# fpga03-serdes-power.net
KiCad netlist of a schematic drawn in Altium Designer
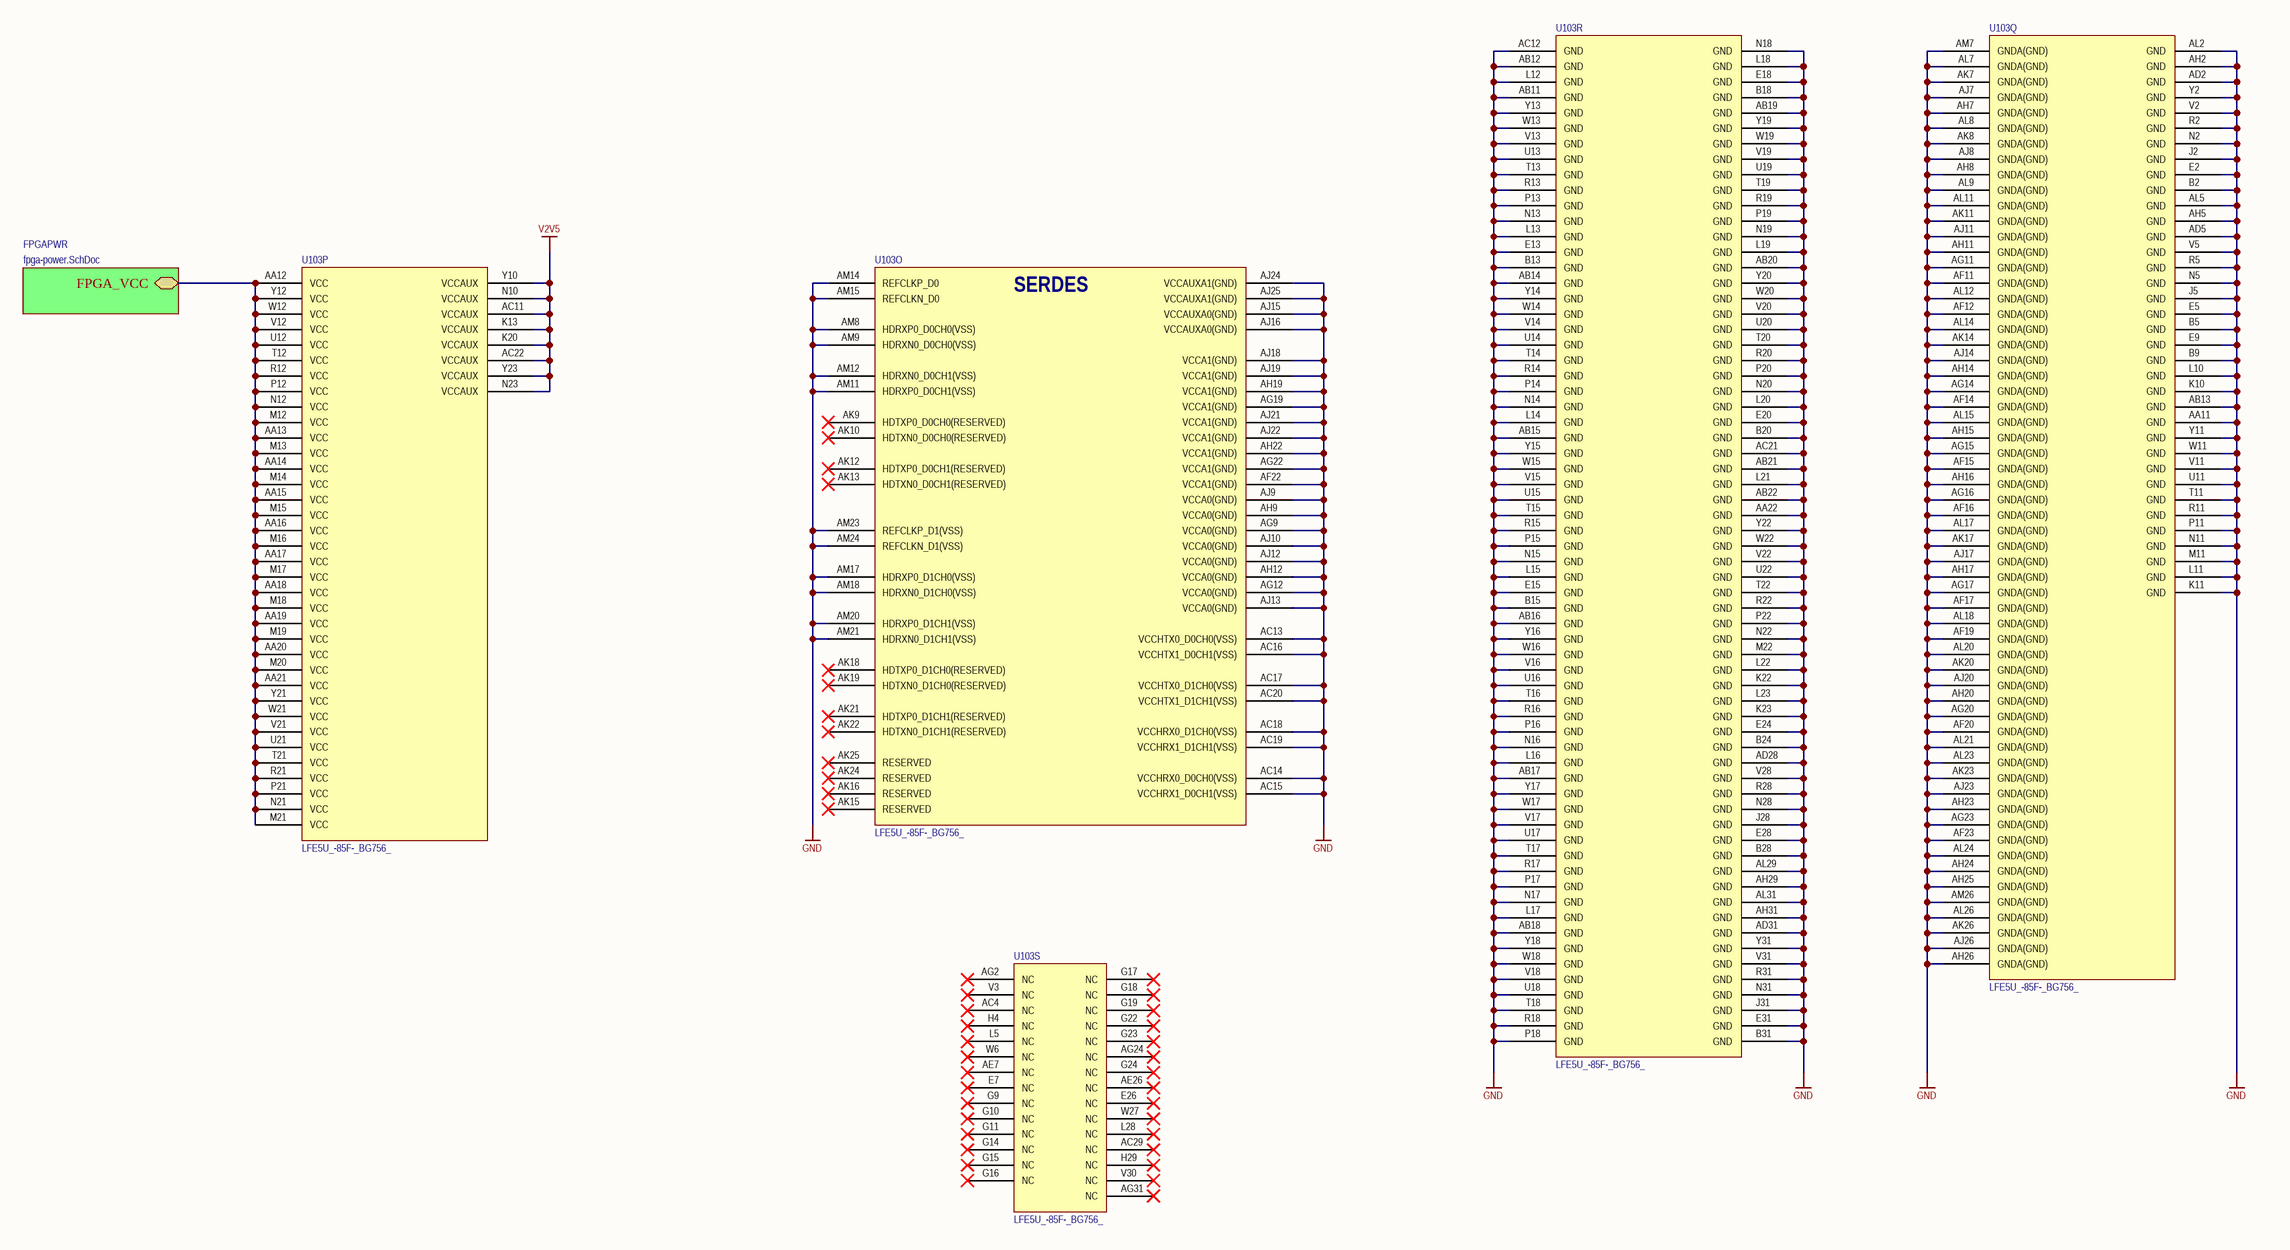
[diagram p0: fpga03-serdes-power.SchDoc]

(export (version "E")
  (design (tool "Eeschema 10.0.6"))
  (components
    (comp (ref "U103")
      (value "LFE5U_-85F-_BG756_")
      (footprint "lattice:caBGA756")
      (description "ECP5 FPGA, 85k LUT, 756-caBGA")
      (fields (field (name "MANUFACTURER") "Lattice Semiconductor"))
      (libsource (lib "lattice") (part "LFE5U_-85F-_BG756_"))
    )
  )
  (nets
    (net (code "1") (name "/FPGA_VCC") (class "Default")
      (node (ref "U103") (pin "AA12") (pinfunction "VCC_AA12") (pintype "power_in"))
      (node (ref "U103") (pin "AA13") (pinfunction "VCC_AA13") (pintype "power_in"))
      (node (ref "U103") (pin "AA14") (pinfunction "VCC_AA14") (pintype "power_in"))
      (node (ref "U103") (pin "AA15") (pinfunction "VCC_AA15") (pintype "power_in"))
      (node (ref "U103") (pin "AA16") (pinfunction "VCC_AA16") (pintype "power_in"))
      (node (ref "U103") (pin "AA17") (pinfunction "VCC_AA17") (pintype "power_in"))
      (node (ref "U103") (pin "AA18") (pinfunction "VCC_AA18") (pintype "power_in"))
      (node (ref "U103") (pin "AA19") (pinfunction "VCC_AA19") (pintype "power_in"))
      (node (ref "U103") (pin "AA20") (pinfunction "VCC_AA20") (pintype "power_in"))
      (node (ref "U103") (pin "AA21") (pinfunction "VCC_AA21") (pintype "power_in"))
      (node (ref "U103") (pin "M12") (pinfunction "VCC_M12") (pintype "power_in"))
      (node (ref "U103") (pin "M13") (pinfunction "VCC_M13") (pintype "power_in"))
      (node (ref "U103") (pin "M14") (pinfunction "VCC_M14") (pintype "power_in"))
      (node (ref "U103") (pin "M15") (pinfunction "VCC_M15") (pintype "power_in"))
      (node (ref "U103") (pin "M16") (pinfunction "VCC_M16") (pintype "power_in"))
      (node (ref "U103") (pin "M17") (pinfunction "VCC_M17") (pintype "power_in"))
      (node (ref "U103") (pin "M18") (pinfunction "VCC_M18") (pintype "power_in"))
      (node (ref "U103") (pin "M19") (pinfunction "VCC_M19") (pintype "power_in"))
      (node (ref "U103") (pin "M20") (pinfunction "VCC_M20") (pintype "power_in"))
      (node (ref "U103") (pin "M21") (pinfunction "VCC_M21") (pintype "power_in"))
      (node (ref "U103") (pin "N12") (pinfunction "VCC_N12") (pintype "power_in"))
      (node (ref "U103") (pin "N21") (pinfunction "VCC_N21") (pintype "power_in"))
      (node (ref "U103") (pin "P12") (pinfunction "VCC_P12") (pintype "power_in"))
      (node (ref "U103") (pin "P21") (pinfunction "VCC_P21") (pintype "power_in"))
      (node (ref "U103") (pin "R12") (pinfunction "VCC_R12") (pintype "power_in"))
      (node (ref "U103") (pin "R21") (pinfunction "VCC_R21") (pintype "power_in"))
      (node (ref "U103") (pin "T12") (pinfunction "VCC_T12") (pintype "power_in"))
      (node (ref "U103") (pin "T21") (pinfunction "VCC_T21") (pintype "power_in"))
      (node (ref "U103") (pin "U12") (pinfunction "VCC_U12") (pintype "power_in"))
      (node (ref "U103") (pin "U21") (pinfunction "VCC_U21") (pintype "power_in"))
      (node (ref "U103") (pin "V12") (pinfunction "VCC_V12") (pintype "power_in"))
      (node (ref "U103") (pin "V21") (pinfunction "VCC_V21") (pintype "power_in"))
      (node (ref "U103") (pin "W12") (pinfunction "VCC_W12") (pintype "power_in"))
      (node (ref "U103") (pin "W21") (pinfunction "VCC_W21") (pintype "power_in"))
      (node (ref "U103") (pin "Y12") (pinfunction "VCC_Y12") (pintype "power_in"))
      (node (ref "U103") (pin "Y21") (pinfunction "VCC_Y21") (pintype "power_in"))
    )
    (net (code "2") (name "GND") (class "Default")
      (node (ref "U103") (pin "AA11") (pinfunction "GND_AA11") (pintype "power_in"))
      (node (ref "U103") (pin "AA22") (pinfunction "GND_AA22") (pintype "power_in"))
      (node (ref "U103") (pin "AB11") (pinfunction "GND_AB11") (pintype "power_in"))
      (node (ref "U103") (pin "AB12") (pinfunction "GND_AB12") (pintype "power_in"))
      (node (ref "U103") (pin "AB13") (pinfunction "GND_AB13") (pintype "power_in"))
      (node (ref "U103") (pin "AB14") (pinfunction "GND_AB14") (pintype "power_in"))
      (node (ref "U103") (pin "AB15") (pinfunction "GND_AB15") (pintype "power_in"))
      (node (ref "U103") (pin "AB16") (pinfunction "GND_AB16") (pintype "power_in"))
      (node (ref "U103") (pin "AB17") (pinfunction "GND_AB17") (pintype "power_in"))
      (node (ref "U103") (pin "AB18") (pinfunction "GND_AB18") (pintype "power_in"))
      (node (ref "U103") (pin "AB19") (pinfunction "GND_AB19") (pintype "power_in"))
      (node (ref "U103") (pin "AB20") (pinfunction "GND_AB20") (pintype "power_in"))
      (node (ref "U103") (pin "AB21") (pinfunction "GND_AB21") (pintype "power_in"))
      (node (ref "U103") (pin "AB22") (pinfunction "GND_AB22") (pintype "power_in"))
      (node (ref "U103") (pin "AC12") (pinfunction "GND_AC12") (pintype "power_in"))
      (node (ref "U103") (pin "AC13") (pinfunction "VCCHTX0_D0CH0(VSS)_AC13") (pintype "power_in"))
      (node (ref "U103") (pin "AC14") (pinfunction "VCCHRX0_D0CH0(VSS)_AC14") (pintype "power_in"))
      (node (ref "U103") (pin "AC15") (pinfunction "VCCHRX1_D0CH1(VSS)_AC15") (pintype "power_in"))
      (node (ref "U103") (pin "AC16") (pinfunction "VCCHTX1_D0CH1(VSS)_AC16") (pintype "power_in"))
      (node (ref "U103") (pin "AC17") (pinfunction "VCCHTX0_D1CH0(VSS)_AC17") (pintype "power_in"))
      (node (ref "U103") (pin "AC18") (pinfunction "VCCHRX0_D1CH0(VSS)_AC18") (pintype "power_in"))
      (node (ref "U103") (pin "AC19") (pinfunction "VCCHRX1_D1CH1(VSS)_AC19") (pintype "power_in"))
      (node (ref "U103") (pin "AC20") (pinfunction "VCCHTX1_D1CH1(VSS)_AC20") (pintype "power_in"))
      (node (ref "U103") (pin "AC21") (pinfunction "GND_AC21") (pintype "power_in"))
      (node (ref "U103") (pin "AD2") (pinfunction "GND_AD2") (pintype "power_in"))
      (node (ref "U103") (pin "AD28") (pinfunction "GND_AD28") (pintype "power_in"))
      (node (ref "U103") (pin "AD31") (pinfunction "GND_AD31") (pintype "power_in"))
      (node (ref "U103") (pin "AD5") (pinfunction "GND_AD5") (pintype "power_in"))
      (node (ref "U103") (pin "AF11") (pinfunction "GNDA(GND)_AF11") (pintype "power_in"))
      (node (ref "U103") (pin "AF12") (pinfunction "GNDA(GND)_AF12") (pintype "power_in"))
      (node (ref "U103") (pin "AF14") (pinfunction "GNDA(GND)_AF14") (pintype "power_in"))
      (node (ref "U103") (pin "AF15") (pinfunction "GNDA(GND)_AF15") (pintype "power_in"))
      (node (ref "U103") (pin "AF16") (pinfunction "GNDA(GND)_AF16") (pintype "power_in"))
      (node (ref "U103") (pin "AF17") (pinfunction "GNDA(GND)_AF17") (pintype "power_in"))
      (node (ref "U103") (pin "AF19") (pinfunction "GNDA(GND)_AF19") (pintype "power_in"))
      (node (ref "U103") (pin "AF20") (pinfunction "GNDA(GND)_AF20") (pintype "power_in"))
      (node (ref "U103") (pin "AF22") (pinfunction "VCCA1(GND)_AF22") (pintype "power_in"))
      (node (ref "U103") (pin "AF23") (pinfunction "GNDA(GND)_AF23") (pintype "power_in"))
      (node (ref "U103") (pin "AG11") (pinfunction "GNDA(GND)_AG11") (pintype "power_in"))
      (node (ref "U103") (pin "AG12") (pinfunction "VCCA0(GND)_AG12") (pintype "power_in"))
      (node (ref "U103") (pin "AG14") (pinfunction "GNDA(GND)_AG14") (pintype "power_in"))
      (node (ref "U103") (pin "AG15") (pinfunction "GNDA(GND)_AG15") (pintype "power_in"))
      (node (ref "U103") (pin "AG16") (pinfunction "GNDA(GND)_AG16") (pintype "power_in"))
      (node (ref "U103") (pin "AG17") (pinfunction "GNDA(GND)_AG17") (pintype "power_in"))
      (node (ref "U103") (pin "AG19") (pinfunction "VCCA1(GND)_AG19") (pintype "power_in"))
      (node (ref "U103") (pin "AG20") (pinfunction "GNDA(GND)_AG20") (pintype "power_in"))
      (node (ref "U103") (pin "AG22") (pinfunction "VCCA1(GND)_AG22") (pintype "power_in"))
      (node (ref "U103") (pin "AG23") (pinfunction "GNDA(GND)_AG23") (pintype "power_in"))
      (node (ref "U103") (pin "AG9") (pinfunction "VCCA0(GND)_AG9") (pintype "power_in"))
      (node (ref "U103") (pin "AH11") (pinfunction "GNDA(GND)_AH11") (pintype "power_in"))
      (node (ref "U103") (pin "AH12") (pinfunction "VCCA0(GND)_AH12") (pintype "power_in"))
      (node (ref "U103") (pin "AH14") (pinfunction "GNDA(GND)_AH14") (pintype "power_in"))
      (node (ref "U103") (pin "AH15") (pinfunction "GNDA(GND)_AH15") (pintype "power_in"))
      (node (ref "U103") (pin "AH16") (pinfunction "GNDA(GND)_AH16") (pintype "power_in"))
      (node (ref "U103") (pin "AH17") (pinfunction "GNDA(GND)_AH17") (pintype "power_in"))
      (node (ref "U103") (pin "AH19") (pinfunction "VCCA1(GND)_AH19") (pintype "power_in"))
      (node (ref "U103") (pin "AH2") (pinfunction "GND_AH2") (pintype "power_in"))
      (node (ref "U103") (pin "AH20") (pinfunction "GNDA(GND)_AH20") (pintype "power_in"))
      (node (ref "U103") (pin "AH22") (pinfunction "VCCA1(GND)_AH22") (pintype "power_in"))
      (node (ref "U103") (pin "AH23") (pinfunction "GNDA(GND)_AH23") (pintype "power_in"))
      (node (ref "U103") (pin "AH24") (pinfunction "GNDA(GND)_AH24") (pintype "power_in"))
      (node (ref "U103") (pin "AH25") (pinfunction "GNDA(GND)_AH25") (pintype "power_in"))
      (node (ref "U103") (pin "AH26") (pinfunction "GNDA(GND)_AH26") (pintype "power_in"))
      (node (ref "U103") (pin "AH29") (pinfunction "GND_AH29") (pintype "power_in"))
      (node (ref "U103") (pin "AH31") (pinfunction "GND_AH31") (pintype "power_in"))
      (node (ref "U103") (pin "AH5") (pinfunction "GND_AH5") (pintype "power_in"))
      (node (ref "U103") (pin "AH7") (pinfunction "GNDA(GND)_AH7") (pintype "power_in"))
      (node (ref "U103") (pin "AH8") (pinfunction "GNDA(GND)_AH8") (pintype "power_in"))
      (node (ref "U103") (pin "AH9") (pinfunction "VCCA0(GND)_AH9") (pintype "power_in"))
      (node (ref "U103") (pin "AJ10") (pinfunction "VCCA0(GND)_AJ10") (pintype "power_in"))
      (node (ref "U103") (pin "AJ11") (pinfunction "GNDA(GND)_AJ11") (pintype "power_in"))
      (node (ref "U103") (pin "AJ12") (pinfunction "VCCA0(GND)_AJ12") (pintype "power_in"))
      (node (ref "U103") (pin "AJ13") (pinfunction "VCCA0(GND)_AJ13") (pintype "power_in"))
      (node (ref "U103") (pin "AJ14") (pinfunction "GNDA(GND)_AJ14") (pintype "power_in"))
      (node (ref "U103") (pin "AJ15") (pinfunction "VCCAUXA0(GND)_AJ15") (pintype "power_in"))
      (node (ref "U103") (pin "AJ16") (pinfunction "VCCAUXA0(GND)_AJ16") (pintype "power_in"))
      (node (ref "U103") (pin "AJ17") (pinfunction "GNDA(GND)_AJ17") (pintype "power_in"))
      (node (ref "U103") (pin "AJ18") (pinfunction "VCCA1(GND)_AJ18") (pintype "power_in"))
      (node (ref "U103") (pin "AJ19") (pinfunction "VCCA1(GND)_AJ19") (pintype "power_in"))
      (node (ref "U103") (pin "AJ20") (pinfunction "GNDA(GND)_AJ20") (pintype "power_in"))
      (node (ref "U103") (pin "AJ21") (pinfunction "VCCA1(GND)_AJ21") (pintype "power_in"))
      (node (ref "U103") (pin "AJ22") (pinfunction "VCCA1(GND)_AJ22") (pintype "power_in"))
      (node (ref "U103") (pin "AJ23") (pinfunction "GNDA(GND)_AJ23") (pintype "power_in"))
      (node (ref "U103") (pin "AJ24") (pinfunction "VCCAUXA1(GND)_AJ24") (pintype "power_in"))
      (node (ref "U103") (pin "AJ25") (pinfunction "VCCAUXA1(GND)_AJ25") (pintype "power_in"))
      (node (ref "U103") (pin "AJ26") (pinfunction "GNDA(GND)_AJ26") (pintype "power_in"))
      (node (ref "U103") (pin "AJ7") (pinfunction "GNDA(GND)_AJ7") (pintype "power_in"))
      (node (ref "U103") (pin "AJ8") (pinfunction "GNDA(GND)_AJ8") (pintype "power_in"))
      (node (ref "U103") (pin "AJ9") (pinfunction "VCCA0(GND)_AJ9") (pintype "power_in"))
      (node (ref "U103") (pin "AK11") (pinfunction "GNDA(GND)_AK11") (pintype "power_in"))
      (node (ref "U103") (pin "AK14") (pinfunction "GNDA(GND)_AK14") (pintype "power_in"))
      (node (ref "U103") (pin "AK17") (pinfunction "GNDA(GND)_AK17") (pintype "power_in"))
      (node (ref "U103") (pin "AK20") (pinfunction "GNDA(GND)_AK20") (pintype "power_in"))
      (node (ref "U103") (pin "AK23") (pinfunction "GNDA(GND)_AK23") (pintype "power_in"))
      (node (ref "U103") (pin "AK26") (pinfunction "GNDA(GND)_AK26") (pintype "power_in"))
      (node (ref "U103") (pin "AK7") (pinfunction "GNDA(GND)_AK7") (pintype "power_in"))
      (node (ref "U103") (pin "AK8") (pinfunction "GNDA(GND)_AK8") (pintype "power_in"))
      (node (ref "U103") (pin "AL11") (pinfunction "GNDA(GND)_AL11") (pintype "power_in"))
      (node (ref "U103") (pin "AL12") (pinfunction "GNDA(GND)_AL12") (pintype "power_in"))
      (node (ref "U103") (pin "AL14") (pinfunction "GNDA(GND)_AL14") (pintype "power_in"))
      (node (ref "U103") (pin "AL15") (pinfunction "GNDA(GND)_AL15") (pintype "power_in"))
      (node (ref "U103") (pin "AL17") (pinfunction "GNDA(GND)_AL17") (pintype "power_in"))
      (node (ref "U103") (pin "AL18") (pinfunction "GNDA(GND)_AL18") (pintype "power_in"))
      (node (ref "U103") (pin "AL2") (pinfunction "GND_AL2") (pintype "power_in"))
      (node (ref "U103") (pin "AL20") (pinfunction "GNDA(GND)_AL20") (pintype "power_in"))
      (node (ref "U103") (pin "AL21") (pinfunction "GNDA(GND)_AL21") (pintype "power_in"))
      (node (ref "U103") (pin "AL23") (pinfunction "GNDA(GND)_AL23") (pintype "power_in"))
      (node (ref "U103") (pin "AL24") (pinfunction "GNDA(GND)_AL24") (pintype "power_in"))
      (node (ref "U103") (pin "AL26") (pinfunction "GNDA(GND)_AL26") (pintype "power_in"))
      (node (ref "U103") (pin "AL29") (pinfunction "GND_AL29") (pintype "power_in"))
      (node (ref "U103") (pin "AL31") (pinfunction "GND_AL31") (pintype "power_in"))
      (node (ref "U103") (pin "AL5") (pinfunction "GND_AL5") (pintype "power_in"))
      (node (ref "U103") (pin "AL7") (pinfunction "GNDA(GND)_AL7") (pintype "power_in"))
      (node (ref "U103") (pin "AL8") (pinfunction "GNDA(GND)_AL8") (pintype "power_in"))
      (node (ref "U103") (pin "AL9") (pinfunction "GNDA(GND)_AL9") (pintype "power_in"))
      (node (ref "U103") (pin "AM11") (pinfunction "HDRXP0_D0CH1(VSS)_AM11") (pintype "passive"))
      (node (ref "U103") (pin "AM12") (pinfunction "HDRXN0_D0CH1(VSS)_AM12") (pintype "passive"))
      (node (ref "U103") (pin "AM14") (pinfunction "REFCLKP_D0_AM14") (pintype "passive"))
      (node (ref "U103") (pin "AM15") (pinfunction "REFCLKN_D0_AM15") (pintype "passive"))
      (node (ref "U103") (pin "AM17") (pinfunction "HDRXP0_D1CH0(VSS)_AM17") (pintype "passive"))
      (node (ref "U103") (pin "AM18") (pinfunction "HDRXN0_D1CH0(VSS)_AM18") (pintype "passive"))
      (node (ref "U103") (pin "AM20") (pinfunction "HDRXP0_D1CH1(VSS)_AM20") (pintype "passive"))
      (node (ref "U103") (pin "AM21") (pinfunction "HDRXN0_D1CH1(VSS)_AM21") (pintype "passive"))
      (node (ref "U103") (pin "AM23") (pinfunction "REFCLKP_D1(VSS)_AM23") (pintype "passive"))
      (node (ref "U103") (pin "AM24") (pinfunction "REFCLKN_D1(VSS)_AM24") (pintype "passive"))
      (node (ref "U103") (pin "AM26") (pinfunction "GNDA(GND)_AM26") (pintype "power_in"))
      (node (ref "U103") (pin "AM7") (pinfunction "GNDA(GND)_AM7") (pintype "power_in"))
      (node (ref "U103") (pin "AM8") (pinfunction "HDRXP0_D0CH0(VSS)_AM8") (pintype "passive"))
      (node (ref "U103") (pin "AM9") (pinfunction "HDRXN0_D0CH0(VSS)_AM9") (pintype "passive"))
      (node (ref "U103") (pin "B13") (pinfunction "GND_B13") (pintype "power_in"))
      (node (ref "U103") (pin "B15") (pinfunction "GND_B15") (pintype "power_in"))
      (node (ref "U103") (pin "B18") (pinfunction "GND_B18") (pintype "power_in"))
      (node (ref "U103") (pin "B2") (pinfunction "GND_B2") (pintype "power_in"))
      (node (ref "U103") (pin "B20") (pinfunction "GND_B20") (pintype "power_in"))
      (node (ref "U103") (pin "B24") (pinfunction "GND_B24") (pintype "power_in"))
      (node (ref "U103") (pin "B28") (pinfunction "GND_B28") (pintype "power_in"))
      (node (ref "U103") (pin "B31") (pinfunction "GND_B31") (pintype "power_in"))
      (node (ref "U103") (pin "B5") (pinfunction "GND_B5") (pintype "power_in"))
      (node (ref "U103") (pin "B9") (pinfunction "GND_B9") (pintype "power_in"))
      (node (ref "U103") (pin "E13") (pinfunction "GND_E13") (pintype "power_in"))
      (node (ref "U103") (pin "E15") (pinfunction "GND_E15") (pintype "power_in"))
      (node (ref "U103") (pin "E18") (pinfunction "GND_E18") (pintype "power_in"))
      (node (ref "U103") (pin "E2") (pinfunction "GND_E2") (pintype "power_in"))
      (node (ref "U103") (pin "E20") (pinfunction "GND_E20") (pintype "power_in"))
      (node (ref "U103") (pin "E24") (pinfunction "GND_E24") (pintype "power_in"))
      (node (ref "U103") (pin "E28") (pinfunction "GND_E28") (pintype "power_in"))
      (node (ref "U103") (pin "E31") (pinfunction "GND_E31") (pintype "power_in"))
      (node (ref "U103") (pin "E5") (pinfunction "GND_E5") (pintype "power_in"))
      (node (ref "U103") (pin "E9") (pinfunction "GND_E9") (pintype "power_in"))
      (node (ref "U103") (pin "J2") (pinfunction "GND_J2") (pintype "power_in"))
      (node (ref "U103") (pin "J28") (pinfunction "GND_J28") (pintype "power_in"))
      (node (ref "U103") (pin "J31") (pinfunction "GND_J31") (pintype "power_in"))
      (node (ref "U103") (pin "J5") (pinfunction "GND_J5") (pintype "power_in"))
      (node (ref "U103") (pin "K10") (pinfunction "GND_K10") (pintype "power_in"))
      (node (ref "U103") (pin "K11") (pinfunction "GND_K11") (pintype "power_in"))
      (node (ref "U103") (pin "K22") (pinfunction "GND_K22") (pintype "power_in"))
      (node (ref "U103") (pin "K23") (pinfunction "GND_K23") (pintype "power_in"))
      (node (ref "U103") (pin "L10") (pinfunction "GND_L10") (pintype "power_in"))
      (node (ref "U103") (pin "L11") (pinfunction "GND_L11") (pintype "power_in"))
      (node (ref "U103") (pin "L12") (pinfunction "GND_L12") (pintype "power_in"))
      (node (ref "U103") (pin "L13") (pinfunction "GND_L13") (pintype "power_in"))
      (node (ref "U103") (pin "L14") (pinfunction "GND_L14") (pintype "power_in"))
      (node (ref "U103") (pin "L15") (pinfunction "GND_L15") (pintype "power_in"))
      (node (ref "U103") (pin "L16") (pinfunction "GND_L16") (pintype "power_in"))
      (node (ref "U103") (pin "L17") (pinfunction "GND_L17") (pintype "power_in"))
      (node (ref "U103") (pin "L18") (pinfunction "GND_L18") (pintype "power_in"))
      (node (ref "U103") (pin "L19") (pinfunction "GND_L19") (pintype "power_in"))
      (node (ref "U103") (pin "L20") (pinfunction "GND_L20") (pintype "power_in"))
      (node (ref "U103") (pin "L21") (pinfunction "GND_L21") (pintype "power_in"))
      (node (ref "U103") (pin "L22") (pinfunction "GND_L22") (pintype "power_in"))
      (node (ref "U103") (pin "L23") (pinfunction "GND_L23") (pintype "power_in"))
      (node (ref "U103") (pin "M11") (pinfunction "GND_M11") (pintype "power_in"))
      (node (ref "U103") (pin "M22") (pinfunction "GND_M22") (pintype "power_in"))
      (node (ref "U103") (pin "N11") (pinfunction "GND_N11") (pintype "power_in"))
      (node (ref "U103") (pin "N13") (pinfunction "GND_N13") (pintype "power_in"))
      (node (ref "U103") (pin "N14") (pinfunction "GND_N14") (pintype "power_in"))
      (node (ref "U103") (pin "N15") (pinfunction "GND_N15") (pintype "power_in"))
      (node (ref "U103") (pin "N16") (pinfunction "GND_N16") (pintype "power_in"))
      (node (ref "U103") (pin "N17") (pinfunction "GND_N17") (pintype "power_in"))
      (node (ref "U103") (pin "N18") (pinfunction "GND_N18") (pintype "power_in"))
      (node (ref "U103") (pin "N19") (pinfunction "GND_N19") (pintype "power_in"))
      (node (ref "U103") (pin "N2") (pinfunction "GND_N2") (pintype "power_in"))
      (node (ref "U103") (pin "N20") (pinfunction "GND_N20") (pintype "power_in"))
      (node (ref "U103") (pin "N22") (pinfunction "GND_N22") (pintype "power_in"))
      (node (ref "U103") (pin "N28") (pinfunction "GND_N28") (pintype "power_in"))
      (node (ref "U103") (pin "N31") (pinfunction "GND_N31") (pintype "power_in"))
      (node (ref "U103") (pin "N5") (pinfunction "GND_N5") (pintype "power_in"))
      (node (ref "U103") (pin "P11") (pinfunction "GND_P11") (pintype "power_in"))
      (node (ref "U103") (pin "P13") (pinfunction "GND_P13") (pintype "power_in"))
      (node (ref "U103") (pin "P14") (pinfunction "GND_P14") (pintype "power_in"))
      (node (ref "U103") (pin "P15") (pinfunction "GND_P15") (pintype "power_in"))
      (node (ref "U103") (pin "P16") (pinfunction "GND_P16") (pintype "power_in"))
      (node (ref "U103") (pin "P17") (pinfunction "GND_P17") (pintype "power_in"))
      (node (ref "U103") (pin "P18") (pinfunction "GND_P18") (pintype "power_in"))
      (node (ref "U103") (pin "P19") (pinfunction "GND_P19") (pintype "power_in"))
      (node (ref "U103") (pin "P20") (pinfunction "GND_P20") (pintype "power_in"))
      (node (ref "U103") (pin "P22") (pinfunction "GND_P22") (pintype "power_in"))
      (node (ref "U103") (pin "R11") (pinfunction "GND_R11") (pintype "power_in"))
      (node (ref "U103") (pin "R13") (pinfunction "GND_R13") (pintype "power_in"))
      (node (ref "U103") (pin "R14") (pinfunction "GND_R14") (pintype "power_in"))
      (node (ref "U103") (pin "R15") (pinfunction "GND_R15") (pintype "power_in"))
      (node (ref "U103") (pin "R16") (pinfunction "GND_R16") (pintype "power_in"))
      (node (ref "U103") (pin "R17") (pinfunction "GND_R17") (pintype "power_in"))
      (node (ref "U103") (pin "R18") (pinfunction "GND_R18") (pintype "power_in"))
      (node (ref "U103") (pin "R19") (pinfunction "GND_R19") (pintype "power_in"))
      (node (ref "U103") (pin "R2") (pinfunction "GND_R2") (pintype "power_in"))
      (node (ref "U103") (pin "R20") (pinfunction "GND_R20") (pintype "power_in"))
      (node (ref "U103") (pin "R22") (pinfunction "GND_R22") (pintype "power_in"))
      (node (ref "U103") (pin "R28") (pinfunction "GND_R28") (pintype "power_in"))
      (node (ref "U103") (pin "R31") (pinfunction "GND_R31") (pintype "power_in"))
      (node (ref "U103") (pin "R5") (pinfunction "GND_R5") (pintype "power_in"))
      (node (ref "U103") (pin "T11") (pinfunction "GND_T11") (pintype "power_in"))
      (node (ref "U103") (pin "T13") (pinfunction "GND_T13") (pintype "power_in"))
      (node (ref "U103") (pin "T14") (pinfunction "GND_T14") (pintype "power_in"))
      (node (ref "U103") (pin "T15") (pinfunction "GND_T15") (pintype "power_in"))
      (node (ref "U103") (pin "T16") (pinfunction "GND_T16") (pintype "power_in"))
      (node (ref "U103") (pin "T17") (pinfunction "GND_T17") (pintype "power_in"))
      (node (ref "U103") (pin "T18") (pinfunction "GND_T18") (pintype "power_in"))
      (node (ref "U103") (pin "T19") (pinfunction "GND_T19") (pintype "power_in"))
      (node (ref "U103") (pin "T20") (pinfunction "GND_T20") (pintype "power_in"))
      (node (ref "U103") (pin "T22") (pinfunction "GND_T22") (pintype "power_in"))
      (node (ref "U103") (pin "U11") (pinfunction "GND_U11") (pintype "power_in"))
      (node (ref "U103") (pin "U13") (pinfunction "GND_U13") (pintype "power_in"))
      (node (ref "U103") (pin "U14") (pinfunction "GND_U14") (pintype "power_in"))
      (node (ref "U103") (pin "U15") (pinfunction "GND_U15") (pintype "power_in"))
      (node (ref "U103") (pin "U16") (pinfunction "GND_U16") (pintype "power_in"))
      (node (ref "U103") (pin "U17") (pinfunction "GND_U17") (pintype "power_in"))
      (node (ref "U103") (pin "U18") (pinfunction "GND_U18") (pintype "power_in"))
      (node (ref "U103") (pin "U19") (pinfunction "GND_U19") (pintype "power_in"))
      (node (ref "U103") (pin "U20") (pinfunction "GND_U20") (pintype "power_in"))
      (node (ref "U103") (pin "U22") (pinfunction "GND_U22") (pintype "power_in"))
      (node (ref "U103") (pin "V11") (pinfunction "GND_V11") (pintype "power_in"))
      (node (ref "U103") (pin "V13") (pinfunction "GND_V13") (pintype "power_in"))
      (node (ref "U103") (pin "V14") (pinfunction "GND_V14") (pintype "power_in"))
      (node (ref "U103") (pin "V15") (pinfunction "GND_V15") (pintype "power_in"))
      (node (ref "U103") (pin "V16") (pinfunction "GND_V16") (pintype "power_in"))
      (node (ref "U103") (pin "V17") (pinfunction "GND_V17") (pintype "power_in"))
      (node (ref "U103") (pin "V18") (pinfunction "GND_V18") (pintype "power_in"))
      (node (ref "U103") (pin "V19") (pinfunction "GND_V19") (pintype "power_in"))
      (node (ref "U103") (pin "V2") (pinfunction "GND_V2") (pintype "power_in"))
      (node (ref "U103") (pin "V20") (pinfunction "GND_V20") (pintype "power_in"))
      (node (ref "U103") (pin "V22") (pinfunction "GND_V22") (pintype "power_in"))
      (node (ref "U103") (pin "V28") (pinfunction "GND_V28") (pintype "power_in"))
      (node (ref "U103") (pin "V31") (pinfunction "GND_V31") (pintype "power_in"))
      (node (ref "U103") (pin "V5") (pinfunction "GND_V5") (pintype "power_in"))
      (node (ref "U103") (pin "W11") (pinfunction "GND_W11") (pintype "power_in"))
      (node (ref "U103") (pin "W13") (pinfunction "GND_W13") (pintype "power_in"))
      (node (ref "U103") (pin "W14") (pinfunction "GND_W14") (pintype "power_in"))
      (node (ref "U103") (pin "W15") (pinfunction "GND_W15") (pintype "power_in"))
      (node (ref "U103") (pin "W16") (pinfunction "GND_W16") (pintype "power_in"))
      (node (ref "U103") (pin "W17") (pinfunction "GND_W17") (pintype "power_in"))
      (node (ref "U103") (pin "W18") (pinfunction "GND_W18") (pintype "power_in"))
      (node (ref "U103") (pin "W19") (pinfunction "GND_W19") (pintype "power_in"))
      (node (ref "U103") (pin "W20") (pinfunction "GND_W20") (pintype "power_in"))
      (node (ref "U103") (pin "W22") (pinfunction "GND_W22") (pintype "power_in"))
      (node (ref "U103") (pin "Y11") (pinfunction "GND_Y11") (pintype "power_in"))
      (node (ref "U103") (pin "Y13") (pinfunction "GND_Y13") (pintype "power_in"))
      (node (ref "U103") (pin "Y14") (pinfunction "GND_Y14") (pintype "power_in"))
      (node (ref "U103") (pin "Y15") (pinfunction "GND_Y15") (pintype "power_in"))
      (node (ref "U103") (pin "Y16") (pinfunction "GND_Y16") (pintype "power_in"))
      (node (ref "U103") (pin "Y17") (pinfunction "GND_Y17") (pintype "power_in"))
      (node (ref "U103") (pin "Y18") (pinfunction "GND_Y18") (pintype "power_in"))
      (node (ref "U103") (pin "Y19") (pinfunction "GND_Y19") (pintype "power_in"))
      (node (ref "U103") (pin "Y2") (pinfunction "GND_Y2") (pintype "power_in"))
      (node (ref "U103") (pin "Y20") (pinfunction "GND_Y20") (pintype "power_in"))
      (node (ref "U103") (pin "Y22") (pinfunction "GND_Y22") (pintype "power_in"))
      (node (ref "U103") (pin "Y31") (pinfunction "GND_Y31") (pintype "power_in"))
    )
    (net (code "3") (name "V2V5") (class "Default")
      (node (ref "U103") (pin "AC11") (pinfunction "VCCAUX_AC11") (pintype "power_in"))
      (node (ref "U103") (pin "AC22") (pinfunction "VCCAUX_AC22") (pintype "power_in"))
      (node (ref "U103") (pin "K13") (pinfunction "VCCAUX_K13") (pintype "power_in"))
      (node (ref "U103") (pin "K20") (pinfunction "VCCAUX_K20") (pintype "power_in"))
      (node (ref "U103") (pin "N10") (pinfunction "VCCAUX_N10") (pintype "power_in"))
      (node (ref "U103") (pin "N23") (pinfunction "VCCAUX_N23") (pintype "power_in"))
      (node (ref "U103") (pin "Y10") (pinfunction "VCCAUX_Y10") (pintype "power_in"))
      (node (ref "U103") (pin "Y23") (pinfunction "VCCAUX_Y23") (pintype "power_in"))
    )
    (net (code "4") (name "unconnected-(U103O-HDTXN0_D0CH0(RESERVED)-PadAK10)") (class "Default")
      (node (ref "U103") (pin "AK10") (pinfunction "HDTXN0_D0CH0(RESERVED)_AK10") (pintype "passive+no_connect"))
    )
    (net (code "5") (name "unconnected-(U103O-HDTXN0_D0CH1(RESERVED)-PadAK13)") (class "Default")
      (node (ref "U103") (pin "AK13") (pinfunction "HDTXN0_D0CH1(RESERVED)_AK13") (pintype "passive+no_connect"))
    )
    (net (code "6") (name "unconnected-(U103O-HDTXN0_D1CH0(RESERVED)-PadAK19)") (class "Default")
      (node (ref "U103") (pin "AK19") (pinfunction "HDTXN0_D1CH0(RESERVED)_AK19") (pintype "passive+no_connect"))
    )
    (net (code "7") (name "unconnected-(U103O-HDTXN0_D1CH1(RESERVED)-PadAK22)") (class "Default")
      (node (ref "U103") (pin "AK22") (pinfunction "HDTXN0_D1CH1(RESERVED)_AK22") (pintype "passive+no_connect"))
    )
    (net (code "8") (name "unconnected-(U103O-HDTXP0_D0CH0(RESERVED)-PadAK9)") (class "Default")
      (node (ref "U103") (pin "AK9") (pinfunction "HDTXP0_D0CH0(RESERVED)_AK9") (pintype "passive+no_connect"))
    )
    (net (code "9") (name "unconnected-(U103O-HDTXP0_D0CH1(RESERVED)-PadAK12)") (class "Default")
      (node (ref "U103") (pin "AK12") (pinfunction "HDTXP0_D0CH1(RESERVED)_AK12") (pintype "passive+no_connect"))
    )
    (net (code "10") (name "unconnected-(U103O-HDTXP0_D1CH0(RESERVED)-PadAK18)") (class "Default")
      (node (ref "U103") (pin "AK18") (pinfunction "HDTXP0_D1CH0(RESERVED)_AK18") (pintype "passive+no_connect"))
    )
    (net (code "11") (name "unconnected-(U103O-HDTXP0_D1CH1(RESERVED)-PadAK21)") (class "Default")
      (node (ref "U103") (pin "AK21") (pinfunction "HDTXP0_D1CH1(RESERVED)_AK21") (pintype "passive+no_connect"))
    )
    (net (code "12") (name "unconnected-(U103O-RESERVED-PadAK15)") (class "Default")
      (node (ref "U103") (pin "AK15") (pinfunction "RESERVED_AK15") (pintype "passive+no_connect"))
    )
    (net (code "13") (name "unconnected-(U103O-RESERVED-PadAK16)") (class "Default")
      (node (ref "U103") (pin "AK16") (pinfunction "RESERVED_AK16") (pintype "passive+no_connect"))
    )
    (net (code "14") (name "unconnected-(U103O-RESERVED-PadAK24)") (class "Default")
      (node (ref "U103") (pin "AK24") (pinfunction "RESERVED_AK24") (pintype "passive+no_connect"))
    )
    (net (code "15") (name "unconnected-(U103O-RESERVED-PadAK25)") (class "Default")
      (node (ref "U103") (pin "AK25") (pinfunction "RESERVED_AK25") (pintype "passive+no_connect"))
    )
    (net (code "16") (name "unconnected-(U103S-NC-PadAC4)") (class "Default")
      (node (ref "U103") (pin "AC4") (pinfunction "NC_AC4") (pintype "passive+no_connect"))
    )
    (net (code "17") (name "unconnected-(U103S-NC-PadAC29)") (class "Default")
      (node (ref "U103") (pin "AC29") (pinfunction "NC_AC29") (pintype "passive+no_connect"))
    )
    (net (code "18") (name "unconnected-(U103S-NC-PadAE7)") (class "Default")
      (node (ref "U103") (pin "AE7") (pinfunction "NC_AE7") (pintype "passive+no_connect"))
    )
    (net (code "19") (name "unconnected-(U103S-NC-PadAE26)") (class "Default")
      (node (ref "U103") (pin "AE26") (pinfunction "NC_AE26") (pintype "passive+no_connect"))
    )
    (net (code "20") (name "unconnected-(U103S-NC-PadAG2)") (class "Default")
      (node (ref "U103") (pin "AG2") (pinfunction "NC_AG2") (pintype "passive+no_connect"))
    )
    (net (code "21") (name "unconnected-(U103S-NC-PadAG24)") (class "Default")
      (node (ref "U103") (pin "AG24") (pinfunction "NC_AG24") (pintype "passive+no_connect"))
    )
    (net (code "22") (name "unconnected-(U103S-NC-PadAG31)") (class "Default")
      (node (ref "U103") (pin "AG31") (pinfunction "NC_AG31") (pintype "passive+no_connect"))
    )
    (net (code "23") (name "unconnected-(U103S-NC-PadE7)") (class "Default")
      (node (ref "U103") (pin "E7") (pinfunction "NC_E7") (pintype "passive+no_connect"))
    )
    (net (code "24") (name "unconnected-(U103S-NC-PadE26)") (class "Default")
      (node (ref "U103") (pin "E26") (pinfunction "NC_E26") (pintype "passive+no_connect"))
    )
    (net (code "25") (name "unconnected-(U103S-NC-PadG9)") (class "Default")
      (node (ref "U103") (pin "G9") (pinfunction "NC_G9") (pintype "passive+no_connect"))
    )
    (net (code "26") (name "unconnected-(U103S-NC-PadG10)") (class "Default")
      (node (ref "U103") (pin "G10") (pinfunction "NC_G10") (pintype "passive+no_connect"))
    )
    (net (code "27") (name "unconnected-(U103S-NC-PadG11)") (class "Default")
      (node (ref "U103") (pin "G11") (pinfunction "NC_G11") (pintype "passive+no_connect"))
    )
    (net (code "28") (name "unconnected-(U103S-NC-PadG14)") (class "Default")
      (node (ref "U103") (pin "G14") (pinfunction "NC_G14") (pintype "passive+no_connect"))
    )
    (net (code "29") (name "unconnected-(U103S-NC-PadG15)") (class "Default")
      (node (ref "U103") (pin "G15") (pinfunction "NC_G15") (pintype "passive+no_connect"))
    )
    (net (code "30") (name "unconnected-(U103S-NC-PadG16)") (class "Default")
      (node (ref "U103") (pin "G16") (pinfunction "NC_G16") (pintype "passive+no_connect"))
    )
    (net (code "31") (name "unconnected-(U103S-NC-PadG17)") (class "Default")
      (node (ref "U103") (pin "G17") (pinfunction "NC_G17") (pintype "passive+no_connect"))
    )
    (net (code "32") (name "unconnected-(U103S-NC-PadG18)") (class "Default")
      (node (ref "U103") (pin "G18") (pinfunction "NC_G18") (pintype "passive+no_connect"))
    )
    (net (code "33") (name "unconnected-(U103S-NC-PadG19)") (class "Default")
      (node (ref "U103") (pin "G19") (pinfunction "NC_G19") (pintype "passive+no_connect"))
    )
    (net (code "34") (name "unconnected-(U103S-NC-PadG22)") (class "Default")
      (node (ref "U103") (pin "G22") (pinfunction "NC_G22") (pintype "passive+no_connect"))
    )
    (net (code "35") (name "unconnected-(U103S-NC-PadG23)") (class "Default")
      (node (ref "U103") (pin "G23") (pinfunction "NC_G23") (pintype "passive+no_connect"))
    )
    (net (code "36") (name "unconnected-(U103S-NC-PadG24)") (class "Default")
      (node (ref "U103") (pin "G24") (pinfunction "NC_G24") (pintype "passive+no_connect"))
    )
    (net (code "37") (name "unconnected-(U103S-NC-PadH4)") (class "Default")
      (node (ref "U103") (pin "H4") (pinfunction "NC_H4") (pintype "passive+no_connect"))
    )
    (net (code "38") (name "unconnected-(U103S-NC-PadH29)") (class "Default")
      (node (ref "U103") (pin "H29") (pinfunction "NC_H29") (pintype "passive+no_connect"))
    )
    (net (code "39") (name "unconnected-(U103S-NC-PadL5)") (class "Default")
      (node (ref "U103") (pin "L5") (pinfunction "NC_L5") (pintype "passive+no_connect"))
    )
    (net (code "40") (name "unconnected-(U103S-NC-PadL28)") (class "Default")
      (node (ref "U103") (pin "L28") (pinfunction "NC_L28") (pintype "passive+no_connect"))
    )
    (net (code "41") (name "unconnected-(U103S-NC-PadV3)") (class "Default")
      (node (ref "U103") (pin "V3") (pinfunction "NC_V3") (pintype "passive+no_connect"))
    )
    (net (code "42") (name "unconnected-(U103S-NC-PadV30)") (class "Default")
      (node (ref "U103") (pin "V30") (pinfunction "NC_V30") (pintype "passive+no_connect"))
    )
    (net (code "43") (name "unconnected-(U103S-NC-PadW6)") (class "Default")
      (node (ref "U103") (pin "W6") (pinfunction "NC_W6") (pintype "passive+no_connect"))
    )
    (net (code "44") (name "unconnected-(U103S-NC-PadW27)") (class "Default")
      (node (ref "U103") (pin "W27") (pinfunction "NC_W27") (pintype "passive+no_connect"))
    )
  )
)
